# ui_debug.net
KiCad netlist of a schematic drawn in Altium Designer
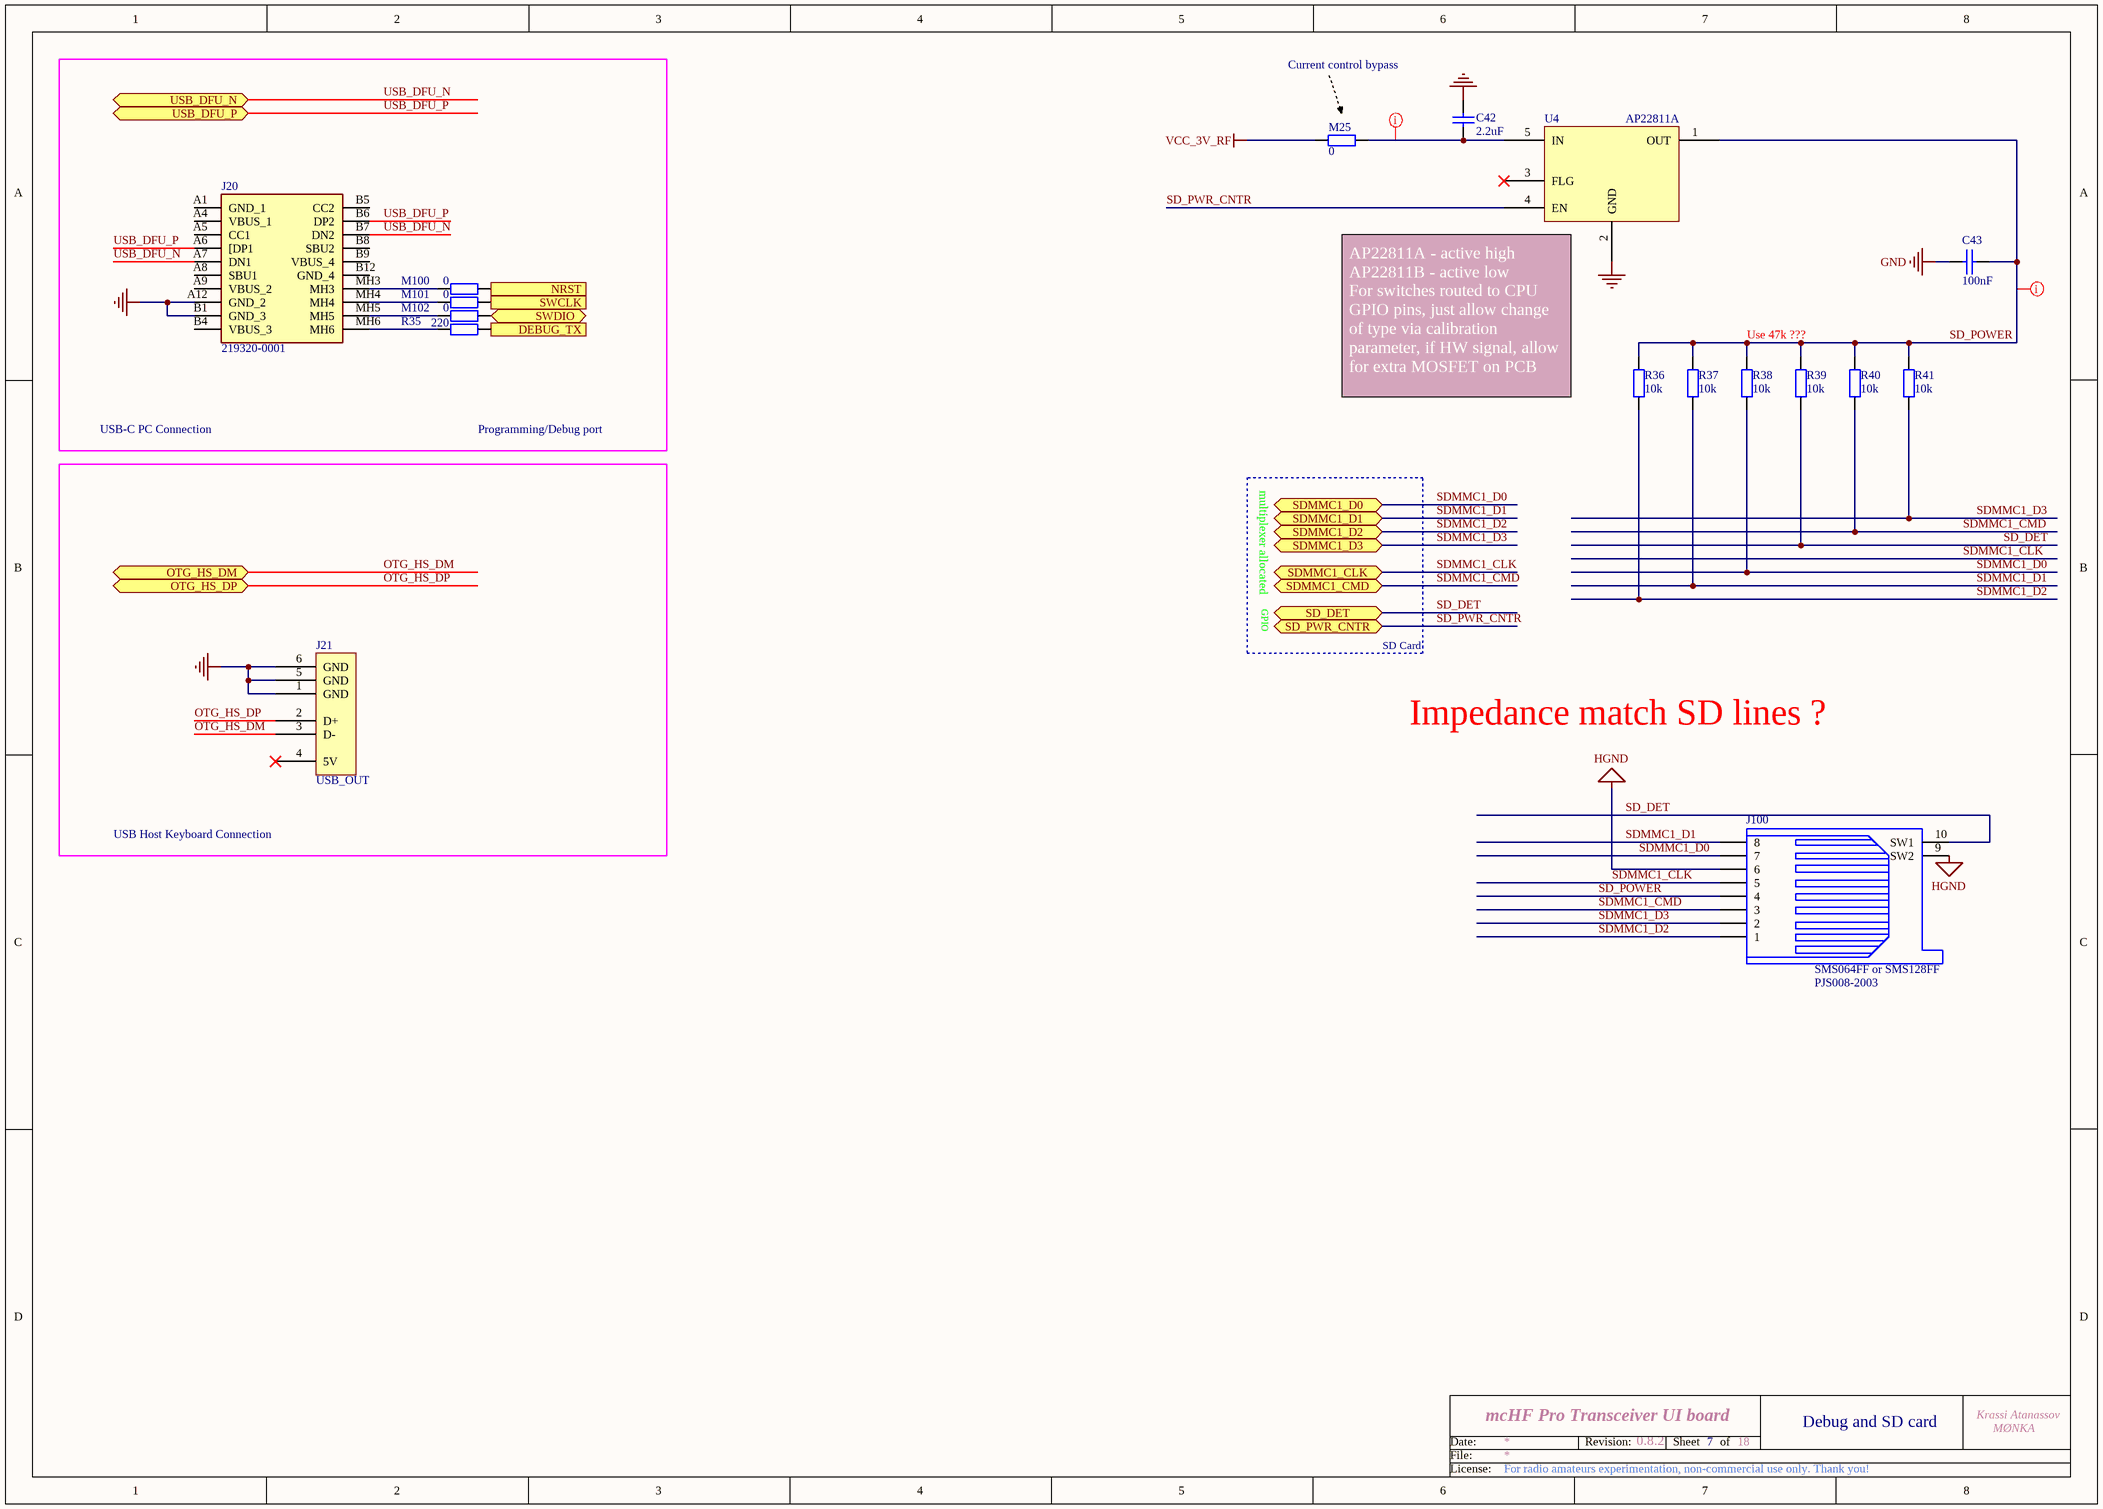
[diagram p0: ui_debug.SchDoc]

(export (version "E")
  (design (tool "Eeschema 10.0.6"))
  (components
    (comp (ref "C42")
      (value "2.2uF")
      (footprint "0805")
      (description "0603  X5R 1礔")
      (fields (field (name "TOLERANCE") "10%"))
      (libsource (lib "MB963_1") (part "CAP SMD 0603  X5R 1礔 25V 10%"))
    )
    (comp (ref "C43")
      (value "100nF")
      (footprint "0805")
      (description "Capacitor")
      (libsource (lib "mcHF_ui") (part "CAP"))
    )
    (comp (ref "J20")
      (value "219320-0001")
      (footprint "2193200001")
      (fields (field (name "MOUSER PART NUMBER") "538-219320-0001"))
      (libsource (lib "219320-0001") (part "219320-0001"))
    )
    (comp (ref "J21")
      (value "USB_OUT")
      (footprint "USB_OUT_A")
      (description "USB Host Connector")
      (libsource (lib "__ui") (part "USB_OUT"))
    )
    (comp (ref "J100")
      (value "PJS008-2003")
      (footprint "PJS008-2003-1")
      (description "Memory Card Connectors MicroSD Card Conn Revrs Mnt Push-Push")
      (libsource (lib "MCD_TOOLS") (part "microSD-PJS008-2003"))
    )
    (comp (ref "M25")
      (value "0")
      (footprint "0805")
      (description "Resistor")
      (libsource (lib "mcHF_rf") (part "RES"))
    )
    (comp (ref "M100")
      (value "0")
      (footprint "0805")
      (description "Resistor")
      (libsource (lib "mcHF_rf") (part "RES"))
    )
    (comp (ref "M101")
      (value "0")
      (footprint "0805")
      (description "Resistor")
      (libsource (lib "mcHF_rf") (part "RES"))
    )
    (comp (ref "M102")
      (value "0")
      (footprint "0805")
      (description "Resistor")
      (libsource (lib "mcHF_rf") (part "RES"))
    )
    (comp (ref "R35")
      (value "220")
      (footprint "0805")
      (description "Resistor")
      (libsource (lib "mcHF_ui") (part "RES"))
    )
    (comp (ref "R36")
      (value "10k")
      (footprint "0805")
      (description "Resistor")
      (libsource (lib "mcHF_ui_b") (part "RES"))
    )
    (comp (ref "R37")
      (value "10k")
      (footprint "0805")
      (description "Resistor")
      (libsource (lib "mcHF_ui_b") (part "RES"))
    )
    (comp (ref "R38")
      (value "10k")
      (footprint "0805")
      (description "Resistor")
      (libsource (lib "mcHF_ui_b") (part "RES"))
    )
    (comp (ref "R39")
      (value "10k")
      (footprint "0805")
      (description "Resistor")
      (libsource (lib "mcHF_ui_b") (part "RES"))
    )
    (comp (ref "R40")
      (value "10k")
      (footprint "0805")
      (description "Resistor")
      (libsource (lib "mcHF_ui_b") (part "RES"))
    )
    (comp (ref "R41")
      (value "10k")
      (footprint "0805")
      (description "Resistor")
      (libsource (lib "mcHF_ui_b") (part "RES"))
    )
    (comp (ref "U4")
      (value "AP22811A")
      (footprint "SOT25-5")
      (description "High-side switch")
      (libsource (lib "__ui") (part "AP22811"))
    )
  )
  (nets
    (net (code "1") (name "/DEBUG_TX") (class "Default")
      (node (ref "R35") (pin "1") (pinfunction "1_1") (pintype "passive"))
    )
    (net (code "2") (name "/NRST") (class "Default")
      (node (ref "M100") (pin "2") (pinfunction "2_2") (pintype "passive"))
    )
    (net (code "3") (name "/OTG_HS_DM") (class "Default")
      (node (ref "J21") (pin "3") (pinfunction "D-_3") (pintype "passive"))
    )
    (net (code "4") (name "/OTG_HS_DP") (class "Default")
      (node (ref "J21") (pin "2") (pinfunction "D+_2") (pintype "passive"))
    )
    (net (code "5") (name "/SDMMC1_CLK") (class "Default")
      (node (ref "J100") (pin "5") (pinfunction "5_5") (pintype "passive"))
    )
    (net (code "6") (name "/SDMMC1_CMD") (class "Default")
      (node (ref "J100") (pin "3") (pinfunction "3_3") (pintype "passive"))
      (node (ref "R40") (pin "2") (pinfunction "2_2") (pintype "passive"))
    )
    (net (code "7") (name "/SDMMC1_D0") (class "Default")
      (node (ref "J100") (pin "7") (pinfunction "7_7") (pintype "passive"))
      (node (ref "R38") (pin "2") (pinfunction "2_2") (pintype "passive"))
    )
    (net (code "8") (name "/SDMMC1_D1") (class "Default")
      (node (ref "J100") (pin "8") (pinfunction "8_8") (pintype "passive"))
      (node (ref "R37") (pin "2") (pinfunction "2_2") (pintype "passive"))
    )
    (net (code "9") (name "/SDMMC1_D2") (class "Default")
      (node (ref "J100") (pin "1") (pinfunction "1_1") (pintype "passive"))
      (node (ref "R36") (pin "2") (pinfunction "2_2") (pintype "passive"))
    )
    (net (code "10") (name "/SDMMC1_D3") (class "Default")
      (node (ref "J100") (pin "2") (pinfunction "2_2") (pintype "passive"))
      (node (ref "R41") (pin "2") (pinfunction "2_2") (pintype "passive"))
    )
    (net (code "11") (name "/SD_DET") (class "Default")
      (node (ref "J100") (pin "10") (pinfunction "SW1_10") (pintype "passive"))
      (node (ref "R39") (pin "2") (pinfunction "2_2") (pintype "passive"))
    )
    (net (code "12") (name "/SD_POWER") (class "Default")
      (node (ref "C43") (pin "1") (pinfunction "1_1") (pintype "passive"))
      (node (ref "J100") (pin "4") (pinfunction "4_4") (pintype "passive"))
      (node (ref "R36") (pin "1") (pinfunction "1_1") (pintype "passive"))
      (node (ref "R37") (pin "1") (pinfunction "1_1") (pintype "passive"))
      (node (ref "R38") (pin "1") (pinfunction "1_1") (pintype "passive"))
      (node (ref "R39") (pin "1") (pinfunction "1_1") (pintype "passive"))
      (node (ref "R40") (pin "1") (pinfunction "1_1") (pintype "passive"))
      (node (ref "R41") (pin "1") (pinfunction "1_1") (pintype "passive"))
      (node (ref "U4") (pin "1") (pinfunction "OUT_1") (pintype "power_in"))
    )
    (net (code "13") (name "/SD_PWR_CNTR") (class "Default")
      (node (ref "U4") (pin "4") (pinfunction "EN_4") (pintype "passive"))
    )
    (net (code "14") (name "/SWCLK") (class "Default")
      (node (ref "M101") (pin "2") (pinfunction "2_2") (pintype "passive"))
    )
    (net (code "15") (name "/SWDIO") (class "Default")
      (node (ref "M102") (pin "2") (pinfunction "2_2") (pintype "passive"))
    )
    (net (code "16") (name "/USB_DFU_N") (class "Default")
      (node (ref "J20") (pin "A7") (pinfunction "DN1_A7") (pintype "passive"))
      (node (ref "J20") (pin "B7") (pinfunction "DN2_B7") (pintype "passive"))
    )
    (net (code "17") (name "/USB_DFU_P") (class "Default")
      (node (ref "J20") (pin "A6") (pinfunction "[DP1_A6") (pintype "passive"))
      (node (ref "J20") (pin "B6") (pinfunction "DP2_B6") (pintype "passive"))
    )
    (net (code "18") (name "GND") (class "Default")
      (node (ref "C42") (pin "1") (pinfunction "1_1") (pintype "passive"))
      (node (ref "C43") (pin "2") (pinfunction "2_2") (pintype "passive"))
      (node (ref "J20") (pin "A12") (pinfunction "GND_2_A12") (pintype "passive"))
      (node (ref "J20") (pin "B1") (pinfunction "GND_3_B1") (pintype "passive"))
      (node (ref "J21") (pin "1") (pinfunction "GND_1") (pintype "passive"))
      (node (ref "J21") (pin "5") (pinfunction "GND_5") (pintype "passive"))
      (node (ref "J21") (pin "6") (pinfunction "GND_6") (pintype "passive"))
      (node (ref "U4") (pin "2") (pinfunction "GND_2") (pintype "passive"))
    )
    (net (code "19") (name "HGND") (class "Default")
      (node (ref "J100") (pin "6") (pinfunction "6_6") (pintype "passive"))
      (node (ref "J100") (pin "9") (pinfunction "SW2_9") (pintype "passive"))
    )
    (net (code "20") (name "Net-(J20-PadMH3)") (class "Default")
      (node (ref "J20") (pin "MH3") (pinfunction "MH3_MH3") (pintype "passive"))
      (node (ref "M100") (pin "1") (pinfunction "1_1") (pintype "passive"))
    )
    (net (code "21") (name "Net-(J20-PadMH4)") (class "Default")
      (node (ref "J20") (pin "MH4") (pinfunction "MH4_MH4") (pintype "passive"))
      (node (ref "M101") (pin "1") (pinfunction "1_1") (pintype "passive"))
    )
    (net (code "22") (name "Net-(J20-PadMH5)") (class "Default")
      (node (ref "J20") (pin "MH5") (pinfunction "MH5_MH5") (pintype "passive"))
      (node (ref "M102") (pin "1") (pinfunction "1_1") (pintype "passive"))
    )
    (net (code "23") (name "Net-(J20-PadMH6)") (class "Default")
      (node (ref "J20") (pin "MH6") (pinfunction "MH6_MH6") (pintype "passive"))
      (node (ref "R35") (pin "2") (pinfunction "2_2") (pintype "passive"))
    )
    (net (code "24") (name "Net-(U4-IN)") (class "Default")
      (node (ref "C42") (pin "2") (pinfunction "2_2") (pintype "passive"))
      (node (ref "M25") (pin "2") (pinfunction "2_2") (pintype "passive"))
      (node (ref "U4") (pin "5") (pinfunction "IN_5") (pintype "power_in"))
    )
    (net (code "25") (name "VCC_3V_RF") (class "Default")
      (node (ref "M25") (pin "1") (pinfunction "1_1") (pintype "passive"))
    )
    (net (code "26") (name "unconnected-(J20-CC1-PadA5)") (class "Default")
      (node (ref "J20") (pin "A5") (pinfunction "CC1_A5") (pintype "passive"))
    )
    (net (code "27") (name "unconnected-(J20-CC2-PadB5)") (class "Default")
      (node (ref "J20") (pin "B5") (pinfunction "CC2_B5") (pintype "passive"))
    )
    (net (code "28") (name "unconnected-(J20-GND_1-PadA1)") (class "Default")
      (node (ref "J20") (pin "A1") (pinfunction "GND_1_A1") (pintype "passive"))
    )
    (net (code "29") (name "unconnected-(J20-GND_4-PadB12)") (class "Default")
      (node (ref "J20") (pin "B12") (pinfunction "GND_4_B12") (pintype "passive"))
    )
    (net (code "30") (name "unconnected-(J20-SBU1-PadA8)") (class "Default")
      (node (ref "J20") (pin "A8") (pinfunction "SBU1_A8") (pintype "passive"))
    )
    (net (code "31") (name "unconnected-(J20-SBU2-PadB8)") (class "Default")
      (node (ref "J20") (pin "B8") (pinfunction "SBU2_B8") (pintype "passive"))
    )
    (net (code "32") (name "unconnected-(J20-VBUS_1-PadA4)") (class "Default")
      (node (ref "J20") (pin "A4") (pinfunction "VBUS_1_A4") (pintype "passive"))
    )
    (net (code "33") (name "unconnected-(J20-VBUS_2-PadA9)") (class "Default")
      (node (ref "J20") (pin "A9") (pinfunction "VBUS_2_A9") (pintype "passive"))
    )
    (net (code "34") (name "unconnected-(J20-VBUS_3-PadB4)") (class "Default")
      (node (ref "J20") (pin "B4") (pinfunction "VBUS_3_B4") (pintype "passive"))
    )
    (net (code "35") (name "unconnected-(J20-VBUS_4-PadB9)") (class "Default")
      (node (ref "J20") (pin "B9") (pinfunction "VBUS_4_B9") (pintype "passive"))
    )
    (net (code "36") (name "unconnected-(J21-5V-Pad4)") (class "Default")
      (node (ref "J21") (pin "4") (pinfunction "5V_4") (pintype "passive+no_connect"))
    )
    (net (code "37") (name "unconnected-(U4-FLG-Pad3)") (class "Default")
      (node (ref "U4") (pin "3") (pinfunction "FLG_3") (pintype "passive+no_connect"))
    )
  )
)
